# Regulated_Power_Supply.net
KiCad netlist of a schematic drawn in EAGLE
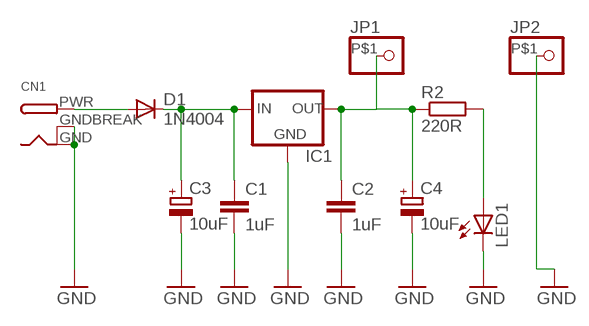
[diagram p0: schematic, sheet 1]

(export (version "E")
  (design (tool "Eeschema 10.0.6"))
  (components
    (comp (ref "C1")
      (value "1uF")
      (footprint "eagle-import:C025-025X050")
      (libsource (lib "eagle-import") (part "C-EU025-025X050"))
    )
    (comp (ref "C2")
      (value "1uF")
      (footprint "eagle-import:C025-025X050")
      (libsource (lib "eagle-import") (part "C-EU025-025X050"))
    )
    (comp (ref "C3")
      (value "10uF")
      (footprint "eagle-import:E1,8-4")
      (libsource (lib "eagle-import") (part "CPOL-EUE1.8-4"))
    )
    (comp (ref "C4")
      (value "10uF")
      (footprint "eagle-import:E1,8-4")
      (libsource (lib "eagle-import") (part "CPOL-EUE1.8-4"))
    )
    (comp (ref "CN1")
      (value "DCBARRELPTH")
      (footprint "eagle-import:DCJACK_2MM_PTH")
      (libsource (lib "eagle-import") (part "DCBARRELPTH"))
    )
    (comp (ref "D1")
      (value "1N4004")
      (footprint "eagle-import:DO41-10")
      (libsource (lib "eagle-import") (part "1N4004"))
    )
    (comp (ref "IC1")
      (value "78XXL")
      (footprint "eagle-import:78XXL")
      (libsource (lib "eagle-import") (part "78XXL"))
    )
    (comp (ref "JP1")
      (value "PINHD-1X1-BIGPOGO")
      (footprint "eagle-import:1X1-BIGPOGO")
      (libsource (lib "eagle-import") (part "PINHD-1X1-BIGPOGO"))
    )
    (comp (ref "JP2")
      (value "PINHD-1X1-BIGPOGO")
      (footprint "eagle-import:1X1-BIGPOGO")
      (libsource (lib "eagle-import") (part "PINHD-1X1-BIGPOGO"))
    )
    (comp (ref "LED1")
      (value "LED5MM")
      (footprint "eagle-import:LED5MM")
      (libsource (lib "eagle-import") (part "LED5MM"))
    )
    (comp (ref "R2")
      (value "220R")
      (footprint "eagle-import:0309V")
      (libsource (lib "eagle-import") (part "R-EU_0309/V"))
    )
  )
  (nets
    (net (code "1") (name "GND") (class "Default")
      (node (ref "C1") (pin "2") (pinfunction "2_2") (pintype "passive"))
      (node (ref "C2") (pin "2") (pinfunction "2_2") (pintype "passive"))
      (node (ref "C3") (pin "-") (pinfunction "-_-") (pintype "passive"))
      (node (ref "C4") (pin "-") (pinfunction "-_-") (pintype "passive"))
      (node (ref "CN1") (pin "GND") (pinfunction "GND_GND") (pintype "power_in"))
      (node (ref "CN1") (pin "GNDBREAK") (pinfunction "GNDBREAK_GNDBREAK") (pintype "power_in"))
      (node (ref "IC1") (pin "GND") (pinfunction "GND_GND") (pintype "input"))
      (node (ref "JP2") (pin "P$1") (pinfunction "1_P$1") (pintype "passive"))
      (node (ref "LED1") (pin "K") (pinfunction "C_K") (pintype "passive"))
    )
    (net (code "2") (name "Net-(C1-Pad1)") (class "Default")
      (node (ref "C1") (pin "1") (pinfunction "1_1") (pintype "passive"))
      (node (ref "C3") (pin "+") (pinfunction "+_+") (pintype "passive"))
      (node (ref "D1") (pin "C") (pinfunction "C_C") (pintype "passive"))
      (node (ref "IC1") (pin "IN") (pinfunction "IN_IN") (pintype "input"))
    )
    (net (code "3") (name "Net-(CN1-PadPWR)") (class "Default")
      (node (ref "CN1") (pin "PWR") (pinfunction "PWR_PWR") (pintype "power_in"))
      (node (ref "D1") (pin "A") (pinfunction "A_A") (pintype "passive"))
    )
    (net (code "4") (name "Net-(JP1-1)") (class "Default")
      (node (ref "C2") (pin "1") (pinfunction "1_1") (pintype "passive"))
      (node (ref "C4") (pin "+") (pinfunction "+_+") (pintype "passive"))
      (node (ref "IC1") (pin "OUT") (pinfunction "OUT_OUT") (pintype "passive"))
      (node (ref "JP1") (pin "P$1") (pinfunction "1_P$1") (pintype "passive"))
      (node (ref "R2") (pin "1") (pinfunction "1_1") (pintype "passive"))
    )
    (net (code "5") (name "Net-(LED1-PadA)") (class "Default")
      (node (ref "LED1") (pin "A") (pinfunction "A_A") (pintype "passive"))
      (node (ref "R2") (pin "2") (pinfunction "2_2") (pintype "passive"))
    )
  )
)
